# sumo_base_5.net
KiCad netlist of a schematic drawn in EAGLE
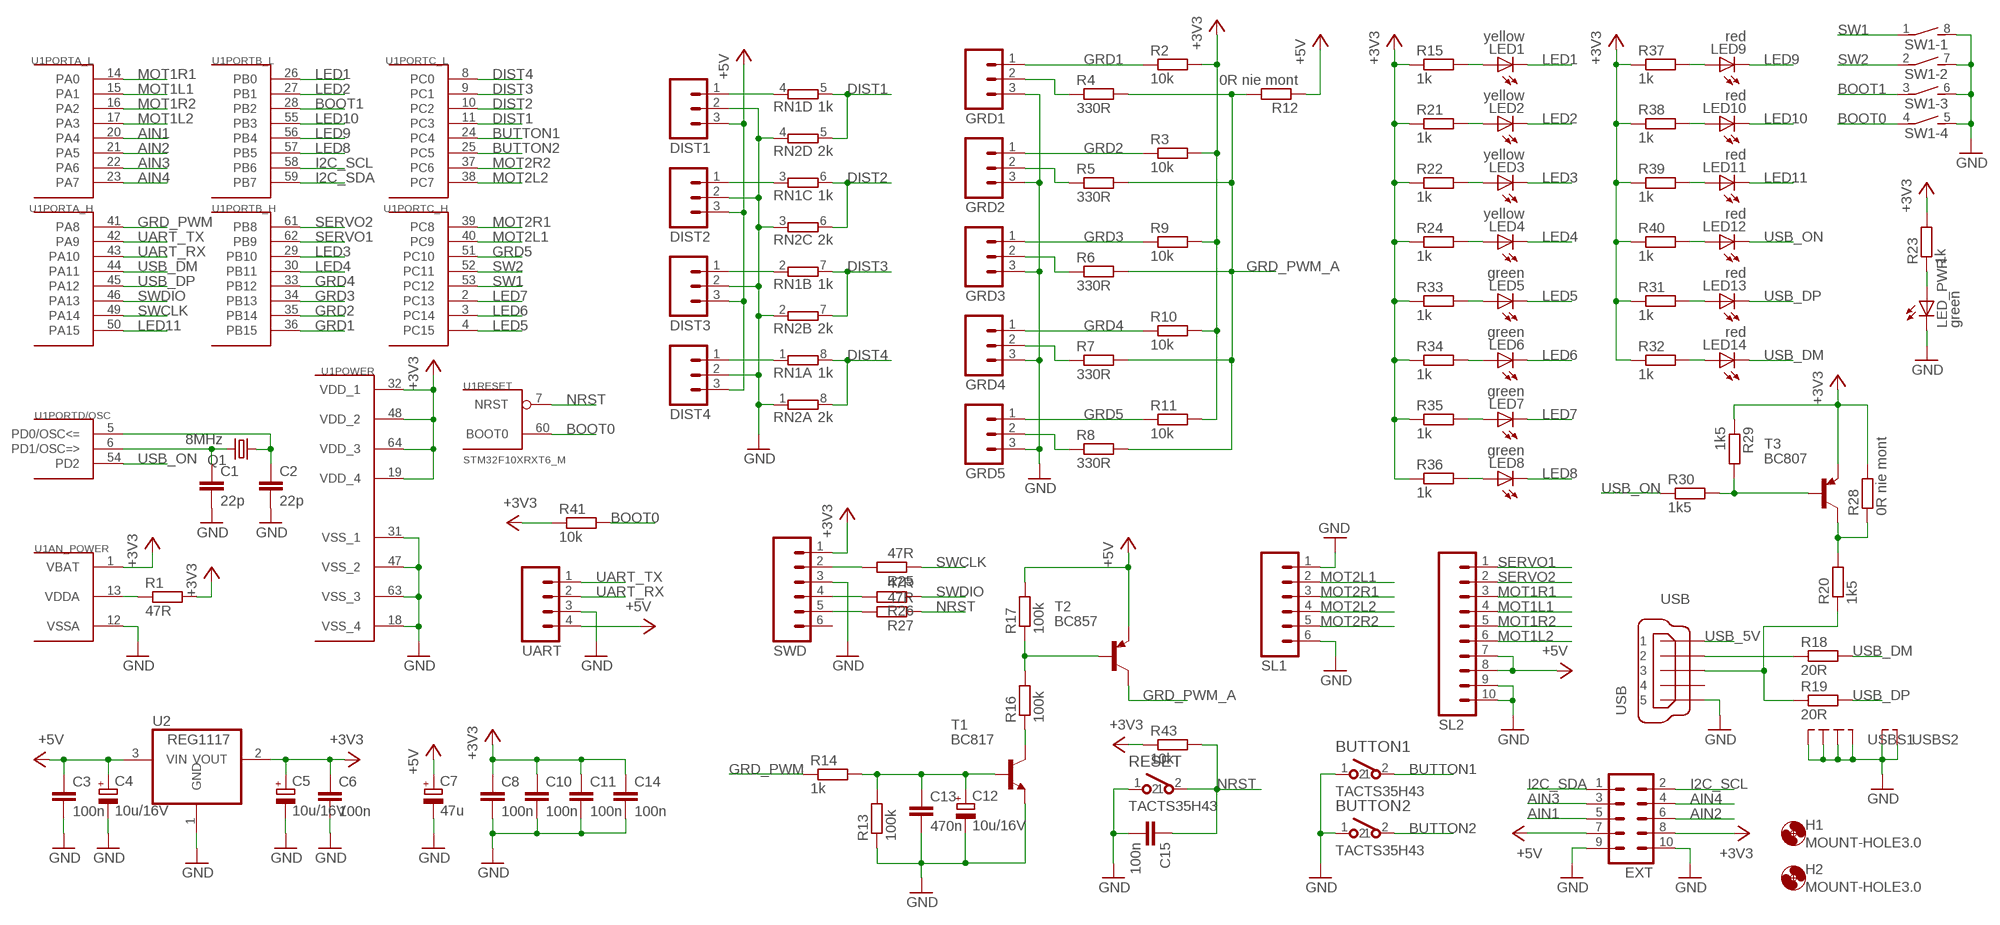
[diagram p0: schematic, sheet 1]

(export (version "E")
  (design (tool "Eeschema 10.0.6"))
  (components
    (comp (ref "BUTTON1")
      (value "TACTS35H43")
      (footprint "eagle-import:TACTS35H43")
      (libsource (lib "eagle-import") (part "TACTS35H43"))
    )
    (comp (ref "BUTTON2")
      (value "TACTS35H43")
      (footprint "eagle-import:TACTS35H43")
      (libsource (lib "eagle-import") (part "TACTS35H43"))
    )
    (comp (ref "C1")
      (value "22p")
      (footprint "eagle-import:C0603")
      (libsource (lib "eagle-import") (part "C-EUC0603"))
    )
    (comp (ref "C2")
      (value "22p")
      (footprint "eagle-import:C0603")
      (libsource (lib "eagle-import") (part "C-EUC0603"))
    )
    (comp (ref "C3")
      (value "100n")
      (footprint "eagle-import:C0603")
      (libsource (lib "eagle-import") (part "C-EUC0603"))
    )
    (comp (ref "C4")
      (value "10u/16V")
      (footprint "eagle-import:SMC_A")
      (libsource (lib "eagle-import") (part "CPOL-EUSMCA"))
    )
    (comp (ref "C5")
      (value "10u/16V")
      (footprint "eagle-import:SMC_A")
      (libsource (lib "eagle-import") (part "CPOL-EUSMCA"))
    )
    (comp (ref "C6")
      (value "100n")
      (footprint "eagle-import:C0603")
      (libsource (lib "eagle-import") (part "C-EUC0603"))
    )
    (comp (ref "C7")
      (value "47u")
      (footprint "eagle-import:SMC_B")
      (libsource (lib "eagle-import") (part "CPOL-EUSMCB"))
    )
    (comp (ref "C8")
      (value "100n")
      (footprint "eagle-import:C0603")
      (libsource (lib "eagle-import") (part "C-EUC0603"))
    )
    (comp (ref "C10")
      (value "100n")
      (footprint "eagle-import:C0603")
      (libsource (lib "eagle-import") (part "C-EUC0603"))
    )
    (comp (ref "C11")
      (value "100n")
      (footprint "eagle-import:C0603")
      (libsource (lib "eagle-import") (part "C-EUC0603"))
    )
    (comp (ref "C12")
      (value "10u/16V")
      (footprint "eagle-import:SMC_A")
      (libsource (lib "eagle-import") (part "CPOL-EUSMCA"))
    )
    (comp (ref "C13")
      (value "470n")
      (footprint "eagle-import:C0603")
      (libsource (lib "eagle-import") (part "C-EUC0603"))
    )
    (comp (ref "C14")
      (value "100n")
      (footprint "eagle-import:C0603")
      (libsource (lib "eagle-import") (part "C-EUC0603"))
    )
    (comp (ref "C15")
      (value "100n")
      (footprint "eagle-import:C0603")
      (libsource (lib "eagle-import") (part "C-EUC0603"))
    )
    (comp (ref "DIST1")
      (value "M03")
      (footprint "eagle-import:03P")
      (libsource (lib "eagle-import") (part "M03"))
    )
    (comp (ref "DIST2")
      (value "M03")
      (footprint "eagle-import:03P")
      (libsource (lib "eagle-import") (part "M03"))
    )
    (comp (ref "DIST3")
      (value "M03")
      (footprint "eagle-import:03P")
      (libsource (lib "eagle-import") (part "M03"))
    )
    (comp (ref "DIST4")
      (value "M03")
      (footprint "eagle-import:03P")
      (libsource (lib "eagle-import") (part "M03"))
    )
    (comp (ref "EXT")
      (value "MA05-2")
      (footprint "eagle-import:MA05-2")
      (libsource (lib "eagle-import") (part "MA05-2"))
    )
    (comp (ref "GRD1")
      (value "M03")
      (footprint "eagle-import:03P")
      (libsource (lib "eagle-import") (part "M03"))
    )
    (comp (ref "GRD2")
      (value "M03")
      (footprint "eagle-import:03P")
      (libsource (lib "eagle-import") (part "M03"))
    )
    (comp (ref "GRD3")
      (value "M03")
      (footprint "eagle-import:03P")
      (libsource (lib "eagle-import") (part "M03"))
    )
    (comp (ref "GRD4")
      (value "M03")
      (footprint "eagle-import:03P")
      (libsource (lib "eagle-import") (part "M03"))
    )
    (comp (ref "GRD5")
      (value "M03")
      (footprint "eagle-import:03P")
      (libsource (lib "eagle-import") (part "M03"))
    )
    (comp (ref "H1")
      (value "MOUNT-HOLE3.0")
      (footprint "eagle-import:3,0")
      (libsource (lib "eagle-import") (part "MOUNT-HOLE3.0"))
    )
    (comp (ref "H2")
      (value "MOUNT-HOLE3.0")
      (footprint "eagle-import:3,0")
      (libsource (lib "eagle-import") (part "MOUNT-HOLE3.0"))
    )
    (comp (ref "LED1")
      (value "yellow")
      (footprint "eagle-import:SML0805")
      (libsource (lib "eagle-import") (part "LEDSML0805"))
    )
    (comp (ref "LED2")
      (value "yellow")
      (footprint "eagle-import:SML0805")
      (libsource (lib "eagle-import") (part "LEDSML0805"))
    )
    (comp (ref "LED3")
      (value "yellow")
      (footprint "eagle-import:SML0805")
      (libsource (lib "eagle-import") (part "LEDSML0805"))
    )
    (comp (ref "LED4")
      (value "yellow")
      (footprint "eagle-import:SML0805")
      (libsource (lib "eagle-import") (part "LEDSML0805"))
    )
    (comp (ref "LED5")
      (value "green")
      (footprint "eagle-import:SML0805")
      (libsource (lib "eagle-import") (part "LEDSML0805"))
    )
    (comp (ref "LED6")
      (value "green")
      (footprint "eagle-import:SML0805")
      (libsource (lib "eagle-import") (part "LEDSML0805"))
    )
    (comp (ref "LED7")
      (value "green")
      (footprint "eagle-import:SML0805")
      (libsource (lib "eagle-import") (part "LEDSML0805"))
    )
    (comp (ref "LED8")
      (value "green")
      (footprint "eagle-import:SML0805")
      (libsource (lib "eagle-import") (part "LEDSML0805"))
    )
    (comp (ref "LED9")
      (value "red")
      (footprint "eagle-import:SML0805")
      (libsource (lib "eagle-import") (part "LEDSML0805"))
    )
    (comp (ref "LED10")
      (value "red")
      (footprint "eagle-import:SML0805")
      (libsource (lib "eagle-import") (part "LEDSML0805"))
    )
    (comp (ref "LED11")
      (value "red")
      (footprint "eagle-import:SML0805")
      (libsource (lib "eagle-import") (part "LEDSML0805"))
    )
    (comp (ref "LED12")
      (value "red")
      (footprint "eagle-import:SML0805")
      (libsource (lib "eagle-import") (part "LEDSML0805"))
    )
    (comp (ref "LED13")
      (value "red")
      (footprint "eagle-import:SML0805")
      (libsource (lib "eagle-import") (part "LEDSML0805"))
    )
    (comp (ref "LED14")
      (value "red")
      (footprint "eagle-import:SML0805")
      (libsource (lib "eagle-import") (part "LEDSML0805"))
    )
    (comp (ref "LED_PWR")
      (value "green")
      (footprint "eagle-import:SML0805")
      (libsource (lib "eagle-import") (part "LEDSML0805"))
    )
    (comp (ref "Q1")
      (value "8MHz")
      (footprint "eagle-import:HC49_S")
      (libsource (lib "eagle-import") (part "CRYSTALHC49S"))
    )
    (comp (ref "R1")
      (value "47R")
      (footprint "eagle-import:R0603")
      (libsource (lib "eagle-import") (part "R-EU_R0603"))
    )
    (comp (ref "R2")
      (value "10k")
      (footprint "eagle-import:R0603")
      (libsource (lib "eagle-import") (part "R-EU_R0603"))
    )
    (comp (ref "R3")
      (value "10k")
      (footprint "eagle-import:R0603")
      (libsource (lib "eagle-import") (part "R-EU_R0603"))
    )
    (comp (ref "R4")
      (value "330R")
      (footprint "eagle-import:R0603")
      (libsource (lib "eagle-import") (part "R-EU_R0603"))
    )
    (comp (ref "R5")
      (value "330R")
      (footprint "eagle-import:R0603")
      (libsource (lib "eagle-import") (part "R-EU_R0603"))
    )
    (comp (ref "R6")
      (value "330R")
      (footprint "eagle-import:R0603")
      (libsource (lib "eagle-import") (part "R-EU_R0603"))
    )
    (comp (ref "R7")
      (value "330R")
      (footprint "eagle-import:R0603")
      (libsource (lib "eagle-import") (part "R-EU_R0603"))
    )
    (comp (ref "R8")
      (value "330R")
      (footprint "eagle-import:R0603")
      (libsource (lib "eagle-import") (part "R-EU_R0603"))
    )
    (comp (ref "R9")
      (value "10k")
      (footprint "eagle-import:R0603")
      (libsource (lib "eagle-import") (part "R-EU_R0603"))
    )
    (comp (ref "R10")
      (value "10k")
      (footprint "eagle-import:R0603")
      (libsource (lib "eagle-import") (part "R-EU_R0603"))
    )
    (comp (ref "R11")
      (value "10k")
      (footprint "eagle-import:R0603")
      (libsource (lib "eagle-import") (part "R-EU_R0603"))
    )
    (comp (ref "R12")
      (value "0R nie mont")
      (footprint "eagle-import:R0603")
      (libsource (lib "eagle-import") (part "R-EU_R0603"))
    )
    (comp (ref "R13")
      (value "100k")
      (footprint "eagle-import:R0603")
      (libsource (lib "eagle-import") (part "R-EU_R0603"))
    )
    (comp (ref "R14")
      (value "1k")
      (footprint "eagle-import:R0603")
      (libsource (lib "eagle-import") (part "R-EU_R0603"))
    )
    (comp (ref "R15")
      (value "1k")
      (footprint "eagle-import:R0603")
      (libsource (lib "eagle-import") (part "R-EU_R0603"))
    )
    (comp (ref "R16")
      (value "100k")
      (footprint "eagle-import:R0603")
      (libsource (lib "eagle-import") (part "R-EU_R0603"))
    )
    (comp (ref "R17")
      (value "100k")
      (footprint "eagle-import:R0603")
      (libsource (lib "eagle-import") (part "R-EU_R0603"))
    )
    (comp (ref "R18")
      (value "20R")
      (footprint "eagle-import:R0603")
      (libsource (lib "eagle-import") (part "R-EU_R0603"))
    )
    (comp (ref "R19")
      (value "20R")
      (footprint "eagle-import:R0603")
      (libsource (lib "eagle-import") (part "R-EU_R0603"))
    )
    (comp (ref "R20")
      (value "1k5")
      (footprint "eagle-import:R0603")
      (libsource (lib "eagle-import") (part "R-EU_R0603"))
    )
    (comp (ref "R21")
      (value "1k")
      (footprint "eagle-import:R0603")
      (libsource (lib "eagle-import") (part "R-EU_R0603"))
    )
    (comp (ref "R22")
      (value "1k")
      (footprint "eagle-import:R0603")
      (libsource (lib "eagle-import") (part "R-EU_R0603"))
    )
    (comp (ref "R23")
      (value "1k")
      (footprint "eagle-import:R0603")
      (libsource (lib "eagle-import") (part "R-EU_R0603"))
    )
    (comp (ref "R24")
      (value "1k")
      (footprint "eagle-import:R0603")
      (libsource (lib "eagle-import") (part "R-EU_R0603"))
    )
    (comp (ref "R25")
      (value "47R")
      (footprint "eagle-import:R0603")
      (libsource (lib "eagle-import") (part "R-EU_R0603"))
    )
    (comp (ref "R26")
      (value "47R")
      (footprint "eagle-import:R0603")
      (libsource (lib "eagle-import") (part "R-EU_R0603"))
    )
    (comp (ref "R27")
      (value "47R")
      (footprint "eagle-import:R0603")
      (libsource (lib "eagle-import") (part "R-EU_R0603"))
    )
    (comp (ref "R28")
      (value "0R nie mont")
      (footprint "eagle-import:R0603")
      (libsource (lib "eagle-import") (part "R-EU_R0603"))
    )
    (comp (ref "R29")
      (value "1k5")
      (footprint "eagle-import:R0603")
      (libsource (lib "eagle-import") (part "R-EU_R0603"))
    )
    (comp (ref "R30")
      (value "1k5")
      (footprint "eagle-import:R0603")
      (libsource (lib "eagle-import") (part "R-EU_R0603"))
    )
    (comp (ref "R31")
      (value "1k")
      (footprint "eagle-import:R0603")
      (libsource (lib "eagle-import") (part "R-EU_R0603"))
    )
    (comp (ref "R32")
      (value "1k")
      (footprint "eagle-import:R0603")
      (libsource (lib "eagle-import") (part "R-EU_R0603"))
    )
    (comp (ref "R33")
      (value "1k")
      (footprint "eagle-import:R0603")
      (libsource (lib "eagle-import") (part "R-EU_R0603"))
    )
    (comp (ref "R34")
      (value "1k")
      (footprint "eagle-import:R0603")
      (libsource (lib "eagle-import") (part "R-EU_R0603"))
    )
    (comp (ref "R35")
      (value "1k")
      (footprint "eagle-import:R0603")
      (libsource (lib "eagle-import") (part "R-EU_R0603"))
    )
    (comp (ref "R36")
      (value "1k")
      (footprint "eagle-import:R0603")
      (libsource (lib "eagle-import") (part "R-EU_R0603"))
    )
    (comp (ref "R37")
      (value "1k")
      (footprint "eagle-import:R0603")
      (libsource (lib "eagle-import") (part "R-EU_R0603"))
    )
    (comp (ref "R38")
      (value "1k")
      (footprint "eagle-import:R0603")
      (libsource (lib "eagle-import") (part "R-EU_R0603"))
    )
    (comp (ref "R39")
      (value "1k")
      (footprint "eagle-import:R0603")
      (libsource (lib "eagle-import") (part "R-EU_R0603"))
    )
    (comp (ref "R40")
      (value "1k")
      (footprint "eagle-import:R0603")
      (libsource (lib "eagle-import") (part "R-EU_R0603"))
    )
    (comp (ref "R41")
      (value "10k")
      (footprint "eagle-import:R0603")
      (libsource (lib "eagle-import") (part "R-EU_R0603"))
    )
    (comp (ref "R43")
      (value "10k")
      (footprint "eagle-import:R0603")
      (libsource (lib "eagle-import") (part "R-EU_R0603"))
    )
    (comp (ref "RESET")
      (value "TACTS35H43")
      (footprint "eagle-import:TACTS35H43")
      (libsource (lib "eagle-import") (part "TACTS35H43"))
    )
    (comp (ref "RN1")
      (value "1k")
      (footprint "eagle-import:CAT16XXX")
      (libsource (lib "eagle-import") (part "CAT16XXXJ4CAT16"))
    )
    (comp (ref "RN2")
      (value "2k")
      (footprint "eagle-import:CAT16XXX")
      (libsource (lib "eagle-import") (part "CAT16XXXJ4CAT16"))
    )
    (comp (ref "SL1")
      (value "M06")
      (footprint "eagle-import:06P")
      (fields (field (name "OC_FARNELL") "unknown") (field (name "OC_NEWARK") "unknown"))
      (libsource (lib "eagle-import") (part "M06"))
    )
    (comp (ref "SL2")
      (value "M10")
      (footprint "eagle-import:10P")
      (fields (field (name "OC_FARNELL") "unknown") (field (name "OC_NEWARK") "unknown"))
      (libsource (lib "eagle-import") (part "M10"))
    )
    (comp (ref "SW1")
      (value "DIP04S")
      (footprint "eagle-import:DIP04S")
      (fields (field (name "OC_FARNELL") "unknown") (field (name "OC_NEWARK") "unknown"))
      (libsource (lib "eagle-import") (part "DIP04S"))
    )
    (comp (ref "SWD")
      (value "M06")
      (footprint "eagle-import:06P")
      (libsource (lib "eagle-import") (part "M06"))
    )
    (comp (ref "T1")
      (value "BC817")
      (footprint "eagle-import:SOT23-BEC")
      (libsource (lib "eagle-import") (part "-NPN-SOT23-BECBC817"))
    )
    (comp (ref "T2")
      (value "BC857")
      (footprint "eagle-import:SOT23-BEC")
      (libsource (lib "eagle-import") (part "-PNP-SOT23-BECBC857C"))
    )
    (comp (ref "T3")
      (value "BC807")
      (footprint "eagle-import:SOT23-BEC")
      (libsource (lib "eagle-import") (part "-PNP-SOT23-BECBC807-16"))
    )
    (comp (ref "U1")
      (value "STM32F10XRXT6_M")
      (footprint "eagle-import:FP64E")
      (libsource (lib "eagle-import") (part "STM32F10XRXT6_M"))
    )
    (comp (ref "U2")
      (value "REG1117")
      (footprint "eagle-import:SOT223")
      (libsource (lib "eagle-import") (part "REG1117"))
    )
    (comp (ref "UART")
      (value "M04")
      (footprint "eagle-import:04P")
      (libsource (lib "eagle-import") (part "M04"))
    )
    (comp (ref "USB")
      (value "USB")
      (footprint "eagle-import:MX47346")
      (libsource (lib "eagle-import") (part "MICRO-USB_5P4S"))
    )
  )
  (nets
    (net (code "1") (name "+3V3") (class "Default")
      (node (ref "C10") (pin "1") (pinfunction "1_1") (pintype "passive"))
      (node (ref "C11") (pin "1") (pinfunction "1_1") (pintype "passive"))
      (node (ref "C14") (pin "1") (pinfunction "1_1") (pintype "passive"))
      (node (ref "C5") (pin "+") (pinfunction "+_+") (pintype "passive"))
      (node (ref "C6") (pin "1") (pinfunction "1_1") (pintype "passive"))
      (node (ref "C8") (pin "1") (pinfunction "1_1") (pintype "passive"))
      (node (ref "EXT") (pin "8") (pinfunction "8_8") (pintype "passive"))
      (node (ref "R1") (pin "2") (pinfunction "2_2") (pintype "passive"))
      (node (ref "R10") (pin "2") (pinfunction "2_2") (pintype "passive"))
      (node (ref "R11") (pin "2") (pinfunction "2_2") (pintype "passive"))
      (node (ref "R15") (pin "1") (pinfunction "1_1") (pintype "passive"))
      (node (ref "R2") (pin "2") (pinfunction "2_2") (pintype "passive"))
      (node (ref "R21") (pin "1") (pinfunction "1_1") (pintype "passive"))
      (node (ref "R22") (pin "1") (pinfunction "1_1") (pintype "passive"))
      (node (ref "R23") (pin "2") (pinfunction "2_2") (pintype "passive"))
      (node (ref "R24") (pin "1") (pinfunction "1_1") (pintype "passive"))
      (node (ref "R28") (pin "2") (pinfunction "2_2") (pintype "passive"))
      (node (ref "R29") (pin "1") (pinfunction "1_1") (pintype "passive"))
      (node (ref "R3") (pin "2") (pinfunction "2_2") (pintype "passive"))
      (node (ref "R31") (pin "1") (pinfunction "1_1") (pintype "passive"))
      (node (ref "R32") (pin "1") (pinfunction "1_1") (pintype "passive"))
      (node (ref "R33") (pin "1") (pinfunction "1_1") (pintype "passive"))
      (node (ref "R34") (pin "1") (pinfunction "1_1") (pintype "passive"))
      (node (ref "R35") (pin "1") (pinfunction "1_1") (pintype "passive"))
      (node (ref "R36") (pin "1") (pinfunction "1_1") (pintype "passive"))
      (node (ref "R37") (pin "1") (pinfunction "1_1") (pintype "passive"))
      (node (ref "R38") (pin "1") (pinfunction "1_1") (pintype "passive"))
      (node (ref "R39") (pin "1") (pinfunction "1_1") (pintype "passive"))
      (node (ref "R40") (pin "1") (pinfunction "1_1") (pintype "passive"))
      (node (ref "R41") (pin "1") (pinfunction "1_1") (pintype "passive"))
      (node (ref "R43") (pin "1") (pinfunction "1_1") (pintype "passive"))
      (node (ref "R9") (pin "2") (pinfunction "2_2") (pintype "passive"))
      (node (ref "SWD") (pin "1") (pinfunction "1_1") (pintype "passive"))
      (node (ref "T3") (pin "E") (pinfunction "E_E") (pintype "passive"))
      (node (ref "U1") (pin "1") (pinfunction "VBAT_1") (pintype "power_in"))
      (node (ref "U1") (pin "19") (pinfunction "VDD_4_19") (pintype "power_in"))
      (node (ref "U1") (pin "32") (pinfunction "VDD_1_32") (pintype "power_in"))
      (node (ref "U1") (pin "48") (pinfunction "VDD_2_48") (pintype "power_in"))
      (node (ref "U1") (pin "64") (pinfunction "VDD_3_64") (pintype "power_in"))
      (node (ref "U2") (pin "2") (pinfunction "VOUT_2") (pintype "output"))
    )
    (net (code "2") (name "+5V") (class "Default")
      (node (ref "C3") (pin "1") (pinfunction "1_1") (pintype "passive"))
      (node (ref "C4") (pin "+") (pinfunction "+_+") (pintype "passive"))
      (node (ref "C7") (pin "+") (pinfunction "+_+") (pintype "passive"))
      (node (ref "DIST1") (pin "3") (pinfunction "3_3") (pintype "passive"))
      (node (ref "DIST2") (pin "3") (pinfunction "3_3") (pintype "passive"))
      (node (ref "DIST3") (pin "3") (pinfunction "3_3") (pintype "passive"))
      (node (ref "DIST4") (pin "3") (pinfunction "3_3") (pintype "passive"))
      (node (ref "EXT") (pin "7") (pinfunction "7_7") (pintype "passive"))
      (node (ref "R12") (pin "1") (pinfunction "1_1") (pintype "passive"))
      (node (ref "R17") (pin "2") (pinfunction "2_2") (pintype "passive"))
      (node (ref "SL2") (pin "7") (pinfunction "7_7") (pintype "passive"))
      (node (ref "SL2") (pin "8") (pinfunction "8_8") (pintype "passive"))
      (node (ref "T2") (pin "E") (pinfunction "E_E") (pintype "passive"))
      (node (ref "U2") (pin "3") (pinfunction "VIN_3") (pintype "input"))
      (node (ref "UART") (pin "4") (pinfunction "4_4") (pintype "passive"))
    )
    (net (code "3") (name "/AIN1") (class "Default")
      (node (ref "EXT") (pin "5") (pinfunction "5_5") (pintype "passive"))
      (node (ref "U1") (pin "20") (pinfunction "PA4_20") (pintype "bidirectional"))
    )
    (net (code "4") (name "/AIN2") (class "Default")
      (node (ref "EXT") (pin "6") (pinfunction "6_6") (pintype "passive"))
      (node (ref "U1") (pin "21") (pinfunction "PA5_21") (pintype "bidirectional"))
    )
    (net (code "5") (name "/AIN3") (class "Default")
      (node (ref "EXT") (pin "3") (pinfunction "3_3") (pintype "passive"))
      (node (ref "U1") (pin "22") (pinfunction "PA6_22") (pintype "bidirectional"))
    )
    (net (code "6") (name "/AIN4") (class "Default")
      (node (ref "EXT") (pin "4") (pinfunction "4_4") (pintype "passive"))
      (node (ref "U1") (pin "23") (pinfunction "PA7_23") (pintype "bidirectional"))
    )
    (net (code "7") (name "/BOOT0") (class "Default")
      (node (ref "R41") (pin "2") (pinfunction "2_2") (pintype "passive"))
      (node (ref "SW1") (pin "4") (pinfunction "1_4") (pintype "passive"))
      (node (ref "U1") (pin "60") (pinfunction "BOOT0_60") (pintype "input"))
    )
    (net (code "8") (name "/BOOT1") (class "Default")
      (node (ref "SW1") (pin "3") (pinfunction "1_3") (pintype "passive"))
      (node (ref "U1") (pin "28") (pinfunction "PB2_28") (pintype "bidirectional"))
    )
    (net (code "9") (name "/BUTTON1") (class "Default")
      (node (ref "BUTTON1") (pin "2") (pinfunction "2_2") (pintype "bidirectional"))
      (node (ref "U1") (pin "24") (pinfunction "PC4_24") (pintype "bidirectional"))
    )
    (net (code "10") (name "/BUTTON2") (class "Default")
      (node (ref "BUTTON2") (pin "2") (pinfunction "2_2") (pintype "bidirectional"))
      (node (ref "U1") (pin "25") (pinfunction "PC5_25") (pintype "bidirectional"))
    )
    (net (code "11") (name "/DIST1") (class "Default")
      (node (ref "RN1") (pin "5") (pinfunction "2_5") (pintype "passive"))
      (node (ref "RN2") (pin "5") (pinfunction "2_5") (pintype "passive"))
      (node (ref "U1") (pin "11") (pinfunction "PC3_11") (pintype "bidirectional"))
    )
    (net (code "12") (name "/DIST2") (class "Default")
      (node (ref "RN1") (pin "6") (pinfunction "2_6") (pintype "passive"))
      (node (ref "RN2") (pin "6") (pinfunction "2_6") (pintype "passive"))
      (node (ref "U1") (pin "10") (pinfunction "PC2_10") (pintype "bidirectional"))
    )
    (net (code "13") (name "/DIST3") (class "Default")
      (node (ref "RN1") (pin "7") (pinfunction "2_7") (pintype "passive"))
      (node (ref "RN2") (pin "7") (pinfunction "2_7") (pintype "passive"))
      (node (ref "U1") (pin "9") (pinfunction "PC1_9") (pintype "bidirectional"))
    )
    (net (code "14") (name "/DIST4") (class "Default")
      (node (ref "RN1") (pin "8") (pinfunction "2_8") (pintype "passive"))
      (node (ref "RN2") (pin "8") (pinfunction "2_8") (pintype "passive"))
      (node (ref "U1") (pin "8") (pinfunction "PC0_8") (pintype "bidirectional"))
    )
    (net (code "15") (name "/GRD1") (class "Default")
      (node (ref "GRD1") (pin "1") (pinfunction "1_1") (pintype "passive"))
      (node (ref "R2") (pin "1") (pinfunction "1_1") (pintype "passive"))
      (node (ref "U1") (pin "36") (pinfunction "PB15_36") (pintype "bidirectional"))
    )
    (net (code "16") (name "/GRD2") (class "Default")
      (node (ref "GRD2") (pin "1") (pinfunction "1_1") (pintype "passive"))
      (node (ref "R3") (pin "1") (pinfunction "1_1") (pintype "passive"))
      (node (ref "U1") (pin "35") (pinfunction "PB14_35") (pintype "bidirectional"))
    )
    (net (code "17") (name "/GRD3") (class "Default")
      (node (ref "GRD3") (pin "1") (pinfunction "1_1") (pintype "passive"))
      (node (ref "R9") (pin "1") (pinfunction "1_1") (pintype "passive"))
      (node (ref "U1") (pin "34") (pinfunction "PB13_34") (pintype "bidirectional"))
    )
    (net (code "18") (name "/GRD4") (class "Default")
      (node (ref "GRD4") (pin "1") (pinfunction "1_1") (pintype "passive"))
      (node (ref "R10") (pin "1") (pinfunction "1_1") (pintype "passive"))
      (node (ref "U1") (pin "33") (pinfunction "PB12_33") (pintype "bidirectional"))
    )
    (net (code "19") (name "/GRD5") (class "Default")
      (node (ref "GRD5") (pin "1") (pinfunction "1_1") (pintype "passive"))
      (node (ref "R11") (pin "1") (pinfunction "1_1") (pintype "passive"))
      (node (ref "U1") (pin "51") (pinfunction "PC10_51") (pintype "bidirectional"))
    )
    (net (code "20") (name "/GRD_PWM") (class "Default")
      (node (ref "R14") (pin "1") (pinfunction "1_1") (pintype "passive"))
      (node (ref "U1") (pin "41") (pinfunction "PA8_41") (pintype "bidirectional"))
    )
    (net (code "21") (name "/GRD_PWM_A") (class "Default")
      (node (ref "R12") (pin "2") (pinfunction "2_2") (pintype "passive"))
      (node (ref "R4") (pin "2") (pinfunction "2_2") (pintype "passive"))
      (node (ref "R5") (pin "2") (pinfunction "2_2") (pintype "passive"))
      (node (ref "R6") (pin "2") (pinfunction "2_2") (pintype "passive"))
      (node (ref "R7") (pin "2") (pinfunction "2_2") (pintype "passive"))
      (node (ref "R8") (pin "2") (pinfunction "2_2") (pintype "passive"))
      (node (ref "T2") (pin "C") (pinfunction "C_C") (pintype "passive"))
    )
    (net (code "22") (name "/I2C_SCL") (class "Default")
      (node (ref "EXT") (pin "2") (pinfunction "2_2") (pintype "passive"))
      (node (ref "U1") (pin "58") (pinfunction "PB6_58") (pintype "bidirectional"))
    )
    (net (code "23") (name "/I2C_SDA") (class "Default")
      (node (ref "EXT") (pin "1") (pinfunction "1_1") (pintype "passive"))
      (node (ref "U1") (pin "59") (pinfunction "PB7_59") (pintype "bidirectional"))
    )
    (net (code "24") (name "/LED1") (class "Default")
      (node (ref "LED1") (pin "C") (pinfunction "C_C") (pintype "passive"))
      (node (ref "U1") (pin "26") (pinfunction "PB0_26") (pintype "bidirectional"))
    )
    (net (code "25") (name "/LED2") (class "Default")
      (node (ref "LED2") (pin "C") (pinfunction "C_C") (pintype "passive"))
      (node (ref "U1") (pin "27") (pinfunction "PB1_27") (pintype "bidirectional"))
    )
    (net (code "26") (name "/LED3") (class "Default")
      (node (ref "LED3") (pin "C") (pinfunction "C_C") (pintype "passive"))
      (node (ref "U1") (pin "29") (pinfunction "PB10_29") (pintype "bidirectional"))
    )
    (net (code "27") (name "/LED4") (class "Default")
      (node (ref "LED4") (pin "C") (pinfunction "C_C") (pintype "passive"))
      (node (ref "U1") (pin "30") (pinfunction "PB11_30") (pintype "bidirectional"))
    )
    (net (code "28") (name "/LED5") (class "Default")
      (node (ref "LED5") (pin "C") (pinfunction "C_C") (pintype "passive"))
      (node (ref "U1") (pin "4") (pinfunction "PC15_4") (pintype "bidirectional"))
    )
    (net (code "29") (name "/LED6") (class "Default")
      (node (ref "LED6") (pin "C") (pinfunction "C_C") (pintype "passive"))
      (node (ref "U1") (pin "3") (pinfunction "PC14_3") (pintype "bidirectional"))
    )
    (net (code "30") (name "/LED7") (class "Default")
      (node (ref "LED7") (pin "C") (pinfunction "C_C") (pintype "passive"))
      (node (ref "U1") (pin "2") (pinfunction "PC13_2") (pintype "bidirectional"))
    )
    (net (code "31") (name "/LED8") (class "Default")
      (node (ref "LED8") (pin "C") (pinfunction "C_C") (pintype "passive"))
      (node (ref "U1") (pin "57") (pinfunction "PB5_57") (pintype "bidirectional"))
    )
    (net (code "32") (name "/LED9") (class "Default")
      (node (ref "LED9") (pin "C") (pinfunction "C_C") (pintype "passive"))
      (node (ref "U1") (pin "56") (pinfunction "PB4_56") (pintype "bidirectional"))
    )
    (net (code "33") (name "/LED10") (class "Default")
      (node (ref "LED10") (pin "C") (pinfunction "C_C") (pintype "passive"))
      (node (ref "U1") (pin "55") (pinfunction "PB3_55") (pintype "bidirectional"))
    )
    (net (code "34") (name "/LED11") (class "Default")
      (node (ref "LED11") (pin "C") (pinfunction "C_C") (pintype "passive"))
      (node (ref "U1") (pin "50") (pinfunction "PA15_50") (pintype "bidirectional"))
    )
    (net (code "35") (name "/MOT1L1") (class "Default")
      (node (ref "SL2") (pin "4") (pinfunction "4_4") (pintype "passive"))
      (node (ref "U1") (pin "15") (pinfunction "PA1_15") (pintype "bidirectional"))
    )
    (net (code "36") (name "/MOT1L2") (class "Default")
      (node (ref "SL2") (pin "6") (pinfunction "6_6") (pintype "passive"))
      (node (ref "U1") (pin "17") (pinfunction "PA3_17") (pintype "bidirectional"))
    )
    (net (code "37") (name "/MOT1R1") (class "Default")
      (node (ref "SL2") (pin "3") (pinfunction "3_3") (pintype "passive"))
      (node (ref "U1") (pin "14") (pinfunction "PA0_14") (pintype "bidirectional"))
    )
    (net (code "38") (name "/MOT1R2") (class "Default")
      (node (ref "SL2") (pin "5") (pinfunction "5_5") (pintype "passive"))
      (node (ref "U1") (pin "16") (pinfunction "PA2_16") (pintype "bidirectional"))
    )
    (net (code "39") (name "/MOT2L1") (class "Default")
      (node (ref "SL1") (pin "2") (pinfunction "2_2") (pintype "passive"))
      (node (ref "U1") (pin "40") (pinfunction "PC9_40") (pintype "bidirectional"))
    )
    (net (code "40") (name "/MOT2L2") (class "Default")
      (node (ref "SL1") (pin "4") (pinfunction "4_4") (pintype "passive"))
      (node (ref "U1") (pin "38") (pinfunction "PC7_38") (pintype "bidirectional"))
    )
    (net (code "41") (name "/MOT2R1") (class "Default")
      (node (ref "SL1") (pin "3") (pinfunction "3_3") (pintype "passive"))
      (node (ref "U1") (pin "39") (pinfunction "PC8_39") (pintype "bidirectional"))
    )
    (net (code "42") (name "/MOT2R2") (class "Default")
      (node (ref "SL1") (pin "5") (pinfunction "5_5") (pintype "passive"))
      (node (ref "U1") (pin "37") (pinfunction "PC6_37") (pintype "bidirectional"))
    )
    (net (code "43") (name "/NRST") (class "Default")
      (node (ref "C15") (pin "1") (pinfunction "1_1") (pintype "passive"))
      (node (ref "R27") (pin "1") (pinfunction "1_1") (pintype "passive"))
      (node (ref "R43") (pin "2") (pinfunction "2_2") (pintype "passive"))
      (node (ref "RESET") (pin "2") (pinfunction "2_2") (pintype "bidirectional"))
      (node (ref "U1") (pin "7") (pinfunction "NRST_7") (pintype "input"))
    )
    (net (code "44") (name "/SERVO1") (class "Default")
      (node (ref "SL2") (pin "1") (pinfunction "1_1") (pintype "passive"))
      (node (ref "U1") (pin "62") (pinfunction "PB9_62") (pintype "bidirectional"))
    )
    (net (code "45") (name "/SERVO2") (class "Default")
      (node (ref "SL2") (pin "2") (pinfunction "2_2") (pintype "passive"))
      (node (ref "U1") (pin "61") (pinfunction "PB8_61") (pintype "bidirectional"))
    )
    (net (code "46") (name "/SW1") (class "Default")
      (node (ref "SW1") (pin "1") (pinfunction "1_1") (pintype "passive"))
      (node (ref "U1") (pin "53") (pinfunction "PC12_53") (pintype "bidirectional"))
    )
    (net (code "47") (name "/SW2") (class "Default")
      (node (ref "SW1") (pin "2") (pinfunction "1_2") (pintype "passive"))
      (node (ref "U1") (pin "52") (pinfunction "PC11_52") (pintype "bidirectional"))
    )
    (net (code "48") (name "/SWCLK") (class "Default")
      (node (ref "R25") (pin "1") (pinfunction "1_1") (pintype "passive"))
      (node (ref "U1") (pin "49") (pinfunction "PA14_49") (pintype "bidirectional"))
    )
    (net (code "49") (name "/SWDIO") (class "Default")
      (node (ref "R26") (pin "1") (pinfunction "1_1") (pintype "passive"))
      (node (ref "U1") (pin "46") (pinfunction "PA13_46") (pintype "bidirectional"))
    )
    (net (code "50") (name "/UART_RX") (class "Default")
      (node (ref "U1") (pin "43") (pinfunction "PA10_43") (pintype "bidirectional"))
      (node (ref "UART") (pin "2") (pinfunction "2_2") (pintype "passive"))
    )
    (net (code "51") (name "/UART_TX") (class "Default")
      (node (ref "U1") (pin "42") (pinfunction "PA9_42") (pintype "bidirectional"))
      (node (ref "UART") (pin "1") (pinfunction "1_1") (pintype "passive"))
    )
    (net (code "52") (name "/USB_5V") (class "Default")
      (node (ref "USB") (pin "1") (pinfunction "1_1") (pintype "passive"))
    )
    (net (code "53") (name "/USB_DM") (class "Default")
      (node (ref "LED14") (pin "C") (pinfunction "C_C") (pintype "passive"))
      (node (ref "R18") (pin "2") (pinfunction "2_2") (pintype "passive"))
      (node (ref "U1") (pin "44") (pinfunction "PA11_44") (pintype "bidirectional"))
    )
    (net (code "54") (name "/USB_DP") (class "Default")
      (node (ref "LED13") (pin "C") (pinfunction "C_C") (pintype "passive"))
      (node (ref "R19") (pin "2") (pinfunction "2_2") (pintype "passive"))
      (node (ref "U1") (pin "45") (pinfunction "PA12_45") (pintype "bidirectional"))
    )
    (net (code "55") (name "/USB_ON") (class "Default")
      (node (ref "LED12") (pin "C") (pinfunction "C_C") (pintype "passive"))
      (node (ref "R30") (pin "1") (pinfunction "1_1") (pintype "passive"))
      (node (ref "U1") (pin "54") (pinfunction "PD2_54") (pintype "bidirectional"))
    )
    (net (code "56") (name "GND") (class "Default")
      (node (ref "BUTTON1") (pin "1") (pinfunction "1_1") (pintype "bidirectional"))
      (node (ref "BUTTON2") (pin "1") (pinfunction "1_1") (pintype "bidirectional"))
      (node (ref "C1") (pin "2") (pinfunction "2_2") (pintype "passive"))
      (node (ref "C10") (pin "2") (pinfunction "2_2") (pintype "passive"))
      (node (ref "C11") (pin "2") (pinfunction "2_2") (pintype "passive"))
      (node (ref "C12") (pin "-") (pinfunction "-_-") (pintype "passive"))
      (node (ref "C13") (pin "2") (pinfunction "2_2") (pintype "passive"))
      (node (ref "C14") (pin "2") (pinfunction "2_2") (pintype "passive"))
      (node (ref "C15") (pin "2") (pinfunction "2_2") (pintype "passive"))
      (node (ref "C2") (pin "2") (pinfunction "2_2") (pintype "passive"))
      (node (ref "C3") (pin "2") (pinfunction "2_2") (pintype "passive"))
      (node (ref "C4") (pin "-") (pinfunction "-_-") (pintype "passive"))
      (node (ref "C5") (pin "-") (pinfunction "-_-") (pintype "passive"))
      (node (ref "C6") (pin "2") (pinfunction "2_2") (pintype "passive"))
      (node (ref "C7") (pin "-") (pinfunction "-_-") (pintype "passive"))
      (node (ref "C8") (pin "2") (pinfunction "2_2") (pintype "passive"))
      (node (ref "DIST1") (pin "2") (pinfunction "2_2") (pintype "passive"))
      (node (ref "DIST2") (pin "2") (pinfunction "2_2") (pintype "passive"))
      (node (ref "DIST3") (pin "2") (pinfunction "2_2") (pintype "passive"))
      (node (ref "DIST4") (pin "2") (pinfunction "2_2") (pintype "passive"))
      (node (ref "EXT") (pin "10") (pinfunction "10_10") (pintype "passive"))
      (node (ref "EXT") (pin "9") (pinfunction "9_9") (pintype "passive"))
      (node (ref "GRD1") (pin "3") (pinfunction "3_3") (pintype "passive"))
      (node (ref "GRD2") (pin "3") (pinfunction "3_3") (pintype "passive"))
      (node (ref "GRD3") (pin "3") (pinfunction "3_3") (pintype "passive"))
      (node (ref "GRD4") (pin "3") (pinfunction "3_3") (pintype "passive"))
      (node (ref "GRD5") (pin "3") (pinfunction "3_3") (pintype "passive"))
      (node (ref "LED_PWR") (pin "C") (pinfunction "C_C") (pintype "passive"))
      (node (ref "R13") (pin "1") (pinfunction "1_1") (pintype "passive"))
      (node (ref "RESET") (pin "1") (pinfunction "1_1") (pintype "bidirectional"))
      (node (ref "RN2") (pin "1") (pinfunction "1_1") (pintype "passive"))
      (node (ref "RN2") (pin "2") (pinfunction "1_2") (pintype "passive"))
      (node (ref "RN2") (pin "3") (pinfunction "1_3") (pintype "passive"))
      (node (ref "RN2") (pin "4") (pinfunction "1_4") (pintype "passive"))
      (node (ref "SL1") (pin "1") (pinfunction "1_1") (pintype "passive"))
      (node (ref "SL1") (pin "6") (pinfunction "6_6") (pintype "passive"))
      (node (ref "SL2") (pin "10") (pinfunction "10_10") (pintype "passive"))
      (node (ref "SL2") (pin "9") (pinfunction "9_9") (pintype "passive"))
      (node (ref "SW1") (pin "5") (pinfunction "2_5") (pintype "passive"))
      (node (ref "SW1") (pin "6") (pinfunction "2_6") (pintype "passive"))
      (node (ref "SW1") (pin "7") (pinfunction "2_7") (pintype "passive"))
      (node (ref "SW1") (pin "8") (pinfunction "2_8") (pintype "passive"))
      (node (ref "SWD") (pin "3") (pinfunction "3_3") (pintype "passive"))
      (node (ref "T1") (pin "E") (pinfunction "E_E") (pintype "passive"))
      (node (ref "U1") (pin "12") (pinfunction "VSSA_12") (pintype "power_in"))
      (node (ref "U1") (pin "18") (pinfunction "VSS_4_18") (pintype "power_in"))
      (node (ref "U1") (pin "31") (pinfunction "VSS_1_31") (pintype "power_in"))
      (node (ref "U1") (pin "47") (pinfunction "VSS_2_47") (pintype "power_in"))
      (node (ref "U1") (pin "63") (pinfunction "VSS_3_63") (pintype "power_in"))
      (node (ref "U2") (pin "1") (pinfunction "GND_1") (pintype "power_in"))
      (node (ref "UART") (pin "3") (pinfunction "3_3") (pintype "passive"))
      (node (ref "USB") (pin "5") (pinfunction "5_5") (pintype "passive"))
      (node (ref "USB") (pin "M1") (pinfunction "S1_M1") (pintype "passive"))
      (node (ref "USB") (pin "M2") (pinfunction "S2_M2") (pintype "passive"))
      (node (ref "USB") (pin "M3") (pinfunction "S3_M3") (pintype "passive"))
      (node (ref "USB") (pin "M4") (pinfunction "S4_M4") (pintype "passive"))
      (node (ref "USB") (pin "M5") (pinfunction "S1_M5") (pintype "passive"))
      (node (ref "USB") (pin "M6") (pinfunction "S2_M6") (pintype "passive"))
    )
    (net (code "57") (name "Net-(C12-Pad+)") (class "Default")
      (node (ref "C12") (pin "+") (pinfunction "+_+") (pintype "passive"))
      (node (ref "C13") (pin "1") (pinfunction "1_1") (pintype "passive"))
      (node (ref "R13") (pin "2") (pinfunction "2_2") (pintype "passive"))
      (node (ref "R14") (pin "2") (pinfunction "2_2") (pintype "passive"))
      (node (ref "T1") (pin "B") (pinfunction "B_B") (pintype "passive"))
    )
    (net (code "58") (name "Net-(DIST4-Pad1)") (class "Default")
      (node (ref "DIST4") (pin "1") (pinfunction "1_1") (pintype "passive"))
      (node (ref "RN1") (pin "1") (pinfunction "1_1") (pintype "passive"))
    )
    (net (code "59") (name "Net-(GRD1-Pad2)") (class "Default")
      (node (ref "GRD1") (pin "2") (pinfunction "2_2") (pintype "passive"))
      (node (ref "R4") (pin "1") (pinfunction "1_1") (pintype "passive"))
    )
    (net (code "60") (name "Net-(GRD2-Pad2)") (class "Default")
      (node (ref "GRD2") (pin "2") (pinfunction "2_2") (pintype "passive"))
      (node (ref "R5") (pin "1") (pinfunction "1_1") (pintype "passive"))
    )
    (net (code "61") (name "Net-(GRD3-Pad2)") (class "Default")
      (node (ref "GRD3") (pin "2") (pinfunction "2_2") (pintype "passive"))
      (node (ref "R6") (pin "1") (pinfunction "1_1") (pintype "passive"))
    )
    (net (code "62") (name "Net-(GRD4-Pad2)") (class "Default")
      (node (ref "GRD4") (pin "2") (pinfunction "2_2") (pintype "passive"))
      (node (ref "R7") (pin "1") (pinfunction "1_1") (pintype "passive"))
    )
    (net (code "63") (name "Net-(GRD5-Pad2)") (class "Default")
      (node (ref "GRD5") (pin "2") (pinfunction "2_2") (pintype "passive"))
      (node (ref "R8") (pin "1") (pinfunction "1_1") (pintype "passive"))
    )
    (net (code "64") (name "Net-(LED1-PadA)") (class "Default")
      (node (ref "LED1") (pin "A") (pinfunction "A_A") (pintype "passive"))
      (node (ref "R15") (pin "2") (pinfunction "2_2") (pintype "passive"))
    )
    (net (code "65") (name "Net-(LED2-PadA)") (class "Default")
      (node (ref "LED2") (pin "A") (pinfunction "A_A") (pintype "passive"))
      (node (ref "R21") (pin "2") (pinfunction "2_2") (pintype "passive"))
    )
    (net (code "66") (name "Net-(LED3-PadA)") (class "Default")
      (node (ref "LED3") (pin "A") (pinfunction "A_A") (pintype "passive"))
      (node (ref "R22") (pin "2") (pinfunction "2_2") (pintype "passive"))
    )
    (net (code "67") (name "Net-(LED4-PadA)") (class "Default")
      (node (ref "LED4") (pin "A") (pinfunction "A_A") (pintype "passive"))
      (node (ref "R24") (pin "2") (pinfunction "2_2") (pintype "passive"))
    )
    (net (code "68") (name "Net-(LED5-PadA)") (class "Default")
      (node (ref "LED5") (pin "A") (pinfunction "A_A") (pintype "passive"))
      (node (ref "R33") (pin "2") (pinfunction "2_2") (pintype "passive"))
    )
    (net (code "69") (name "Net-(LED6-PadA)") (class "Default")
      (node (ref "LED6") (pin "A") (pinfunction "A_A") (pintype "passive"))
      (node (ref "R34") (pin "2") (pinfunction "2_2") (pintype "passive"))
    )
    (net (code "70") (name "Net-(LED7-PadA)") (class "Default")
      (node (ref "LED7") (pin "A") (pinfunction "A_A") (pintype "passive"))
      (node (ref "R35") (pin "2") (pinfunction "2_2") (pintype "passive"))
    )
    (net (code "71") (name "Net-(LED8-PadA)") (class "Default")
      (node (ref "LED8") (pin "A") (pinfunction "A_A") (pintype "passive"))
      (node (ref "R36") (pin "2") (pinfunction "2_2") (pintype "passive"))
    )
    (net (code "72") (name "Net-(LED9-PadA)") (class "Default")
      (node (ref "LED9") (pin "A") (pinfunction "A_A") (pintype "passive"))
      (node (ref "R37") (pin "2") (pinfunction "2_2") (pintype "passive"))
    )
    (net (code "73") (name "Net-(LED10-PadA)") (class "Default")
      (node (ref "LED10") (pin "A") (pinfunction "A_A") (pintype "passive"))
      (node (ref "R38") (pin "2") (pinfunction "2_2") (pintype "passive"))
    )
    (net (code "74") (name "Net-(LED11-PadA)") (class "Default")
      (node (ref "LED11") (pin "A") (pinfunction "A_A") (pintype "passive"))
      (node (ref "R39") (pin "2") (pinfunction "2_2") (pintype "passive"))
    )
    (net (code "75") (name "Net-(LED12-PadA)") (class "Default")
      (node (ref "LED12") (pin "A") (pinfunction "A_A") (pintype "passive"))
      (node (ref "R40") (pin "2") (pinfunction "2_2") (pintype "passive"))
    )
    (net (code "76") (name "Net-(LED13-PadA)") (class "Default")
      (node (ref "LED13") (pin "A") (pinfunction "A_A") (pintype "passive"))
      (node (ref "R31") (pin "2") (pinfunction "2_2") (pintype "passive"))
    )
    (net (code "77") (name "Net-(LED14-PadA)") (class "Default")
      (node (ref "LED14") (pin "A") (pinfunction "A_A") (pintype "passive"))
      (node (ref "R32") (pin "2") (pinfunction "2_2") (pintype "passive"))
    )
    (net (code "78") (name "Net-(LED_PWR-PadA)") (class "Default")
      (node (ref "LED_PWR") (pin "A") (pinfunction "A_A") (pintype "passive"))
      (node (ref "R23") (pin "1") (pinfunction "1_1") (pintype "passive"))
    )
    (net (code "79") (name "Net-(R16-Pad1)") (class "Default")
      (node (ref "R16") (pin "1") (pinfunction "1_1") (pintype "passive"))
      (node (ref "T1") (pin "C") (pinfunction "C_C") (pintype "passive"))
    )
    (net (code "80") (name "Net-(R16-Pad2)") (class "Default")
      (node (ref "R16") (pin "2") (pinfunction "2_2") (pintype "passive"))
      (node (ref "R17") (pin "1") (pinfunction "1_1") (pintype "passive"))
      (node (ref "T2") (pin "B") (pinfunction "B_B") (pintype "passive"))
    )
    (net (code "81") (name "Net-(R18-Pad1)") (class "Default")
      (node (ref "R18") (pin "1") (pinfunction "1_1") (pintype "passive"))
      (node (ref "USB") (pin "2") (pinfunction "2_2") (pintype "passive"))
    )
    (net (code "82") (name "Net-(R19-Pad1)") (class "Default")
      (node (ref "R19") (pin "1") (pinfunction "1_1") (pintype "passive"))
      (node (ref "R20") (pin "1") (pinfunction "1_1") (pintype "passive"))
      (node (ref "USB") (pin "3") (pinfunction "3_3") (pintype "passive"))
    )
    (net (code "83") (name "Net-(R20-Pad2)") (class "Default")
      (node (ref "R20") (pin "2") (pinfunction "2_2") (pintype "passive"))
      (node (ref "R28") (pin "1") (pinfunction "1_1") (pintype "passive"))
      (node (ref "T3") (pin "C") (pinfunction "C_C") (pintype "passive"))
    )
    (net (code "84") (name "Net-(R25-Pad2)") (class "Default")
      (node (ref "R25") (pin "2") (pinfunction "2_2") (pintype "passive"))
      (node (ref "SWD") (pin "2") (pinfunction "2_2") (pintype "passive"))
    )
    (net (code "85") (name "Net-(R26-Pad2)") (class "Default")
      (node (ref "R26") (pin "2") (pinfunction "2_2") (pintype "passive"))
      (node (ref "SWD") (pin "4") (pinfunction "4_4") (pintype "passive"))
    )
    (net (code "86") (name "Net-(R27-Pad2)") (class "Default")
      (node (ref "R27") (pin "2") (pinfunction "2_2") (pintype "passive"))
      (node (ref "SWD") (pin "5") (pinfunction "5_5") (pintype "passive"))
    )
    (net (code "87") (name "Net-(R29-Pad2)") (class "Default")
      (node (ref "R29") (pin "2") (pinfunction "2_2") (pintype "passive"))
      (node (ref "R30") (pin "2") (pinfunction "2_2") (pintype "passive"))
      (node (ref "T3") (pin "B") (pinfunction "B_B") (pintype "passive"))
    )
    (net (code "88") (name "Net-(RN1B-1)") (class "Default")
      (node (ref "DIST3") (pin "1") (pinfunction "1_1") (pintype "passive"))
      (node (ref "RN1") (pin "2") (pinfunction "1_2") (pintype "passive"))
    )
    (net (code "89") (name "Net-(RN1C-1)") (class "Default")
      (node (ref "DIST2") (pin "1") (pinfunction "1_1") (pintype "passive"))
      (node (ref "RN1") (pin "3") (pinfunction "1_3") (pintype "passive"))
    )
    (net (code "90") (name "Net-(RN1D-1)") (class "Default")
      (node (ref "DIST1") (pin "1") (pinfunction "1_1") (pintype "passive"))
      (node (ref "RN1") (pin "4") (pinfunction "1_4") (pintype "passive"))
    )
    (net (code "91") (name "Net-(U1A-VDDA)") (class "Default")
      (node (ref "R1") (pin "1") (pinfunction "1_1") (pintype "passive"))
      (node (ref "U1") (pin "13") (pinfunction "VDDA_13") (pintype "power_in"))
    )
    (net (code "92") (name "Net-(U1H-PD0{slash}OSC<=)") (class "Default")
      (node (ref "C2") (pin "1") (pinfunction "1_1") (pintype "passive"))
      (node (ref "Q1") (pin "1") (pinfunction "1_1") (pintype "passive"))
      (node (ref "U1") (pin "5") (pinfunction "PD0/OSC<=_5") (pintype "bidirectional"))
    )
    (net (code "93") (name "Net-(U1H-PD1{slash}OSC=>)") (class "Default")
      (node (ref "C1") (pin "1") (pinfunction "1_1") (pintype "passive"))
      (node (ref "Q1") (pin "2") (pinfunction "2_2") (pintype "passive"))
      (node (ref "U1") (pin "6") (pinfunction "PD1/OSC=>_6") (pintype "bidirectional"))
    )
    (net (code "94") (name "unconnected-(SWD-Pad6)") (class "Default")
      (node (ref "SWD") (pin "6") (pinfunction "6_6") (pintype "passive"))
    )
    (net (code "95") (name "unconnected-(USB-Pad4)") (class "Default")
      (node (ref "USB") (pin "4") (pinfunction "4_4") (pintype "passive"))
    )
  )
)
